# fdcanusb.net
KiCad netlist of a schematic drawn in EAGLE
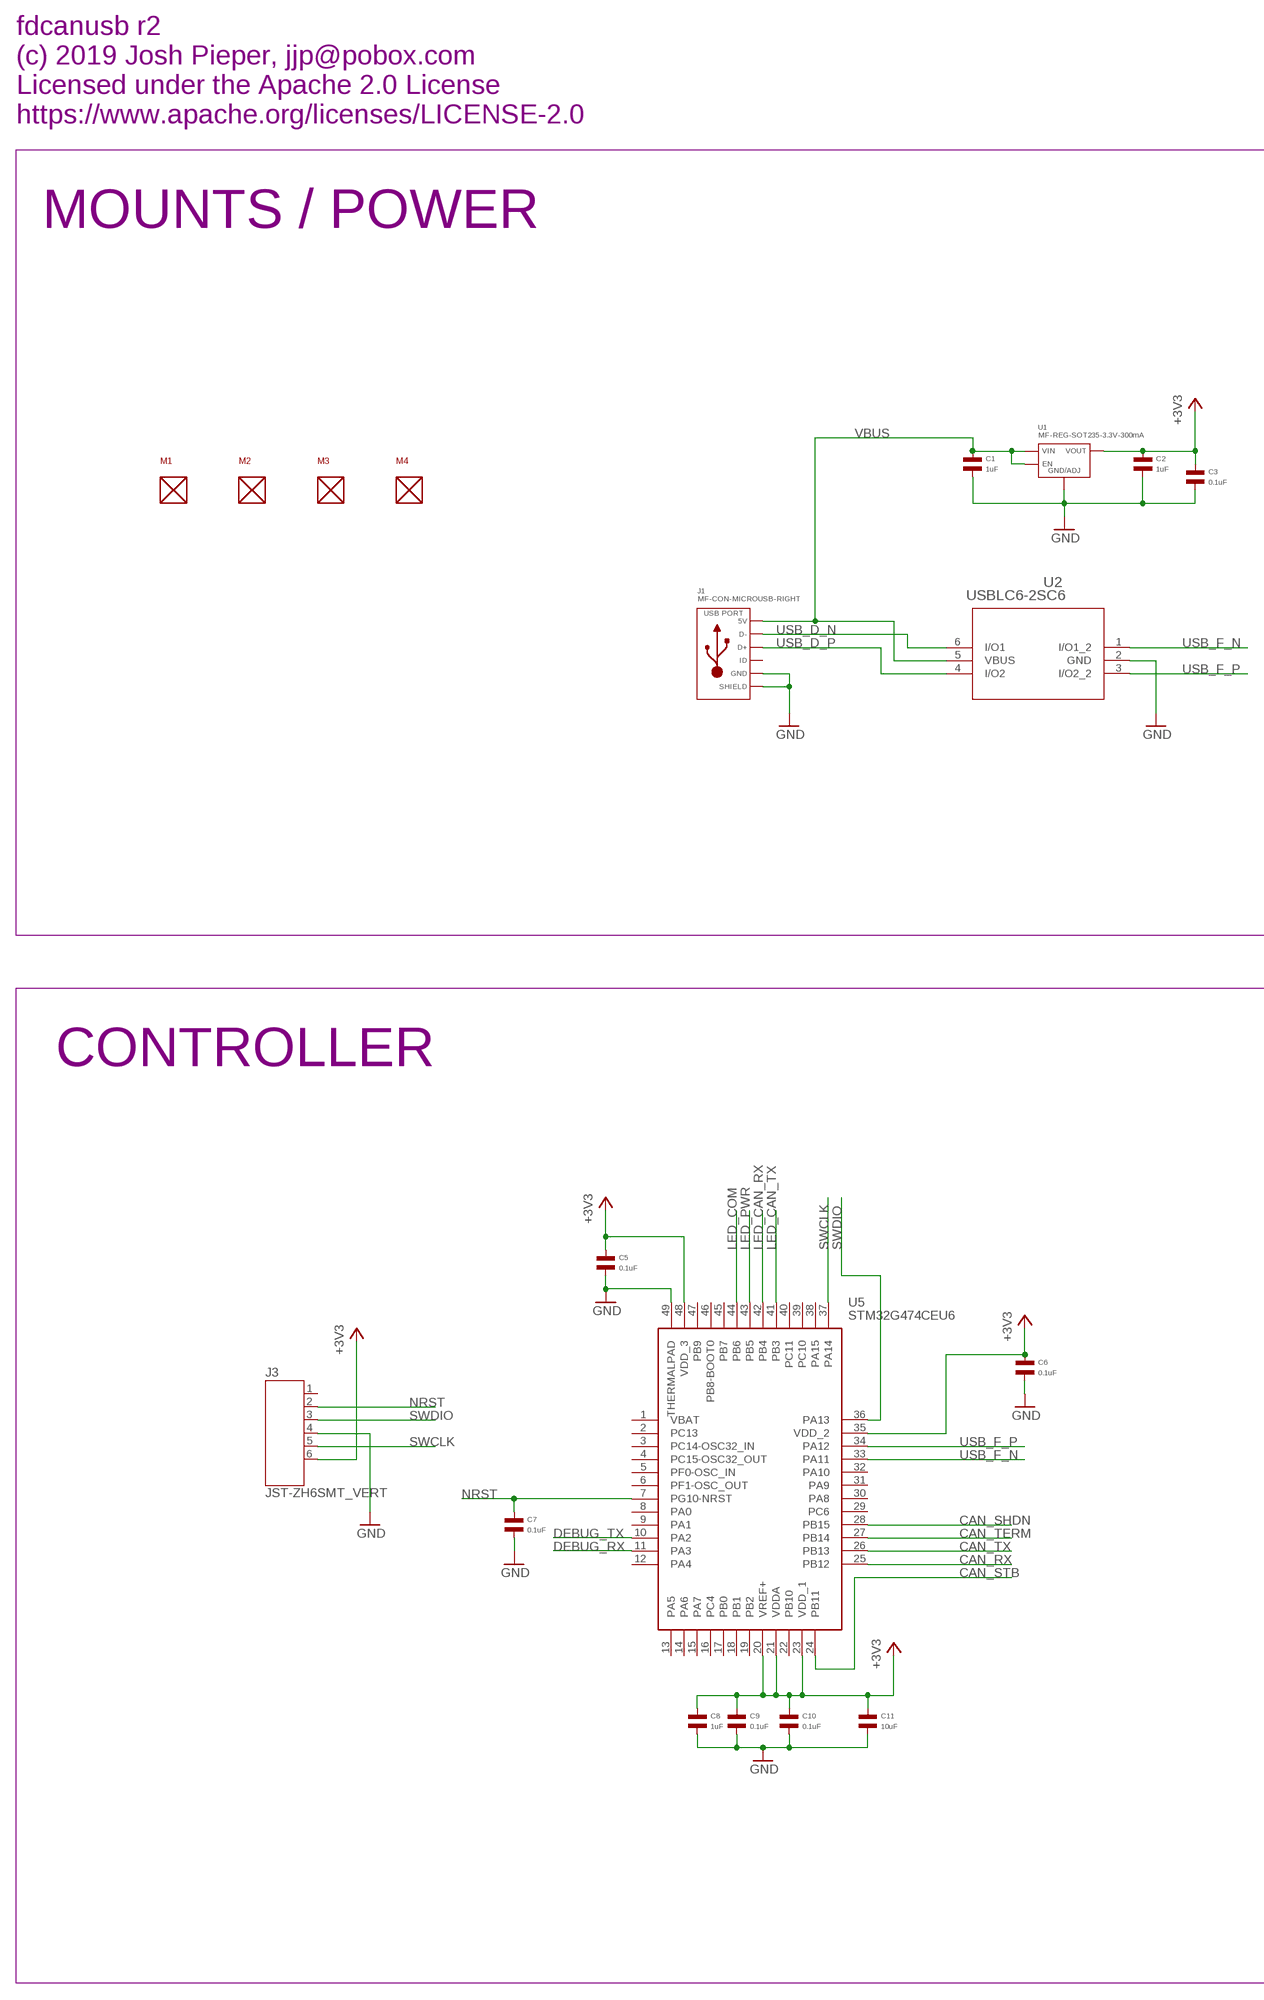
[diagram p0: schematic, sheet 1, part 1 of 2]
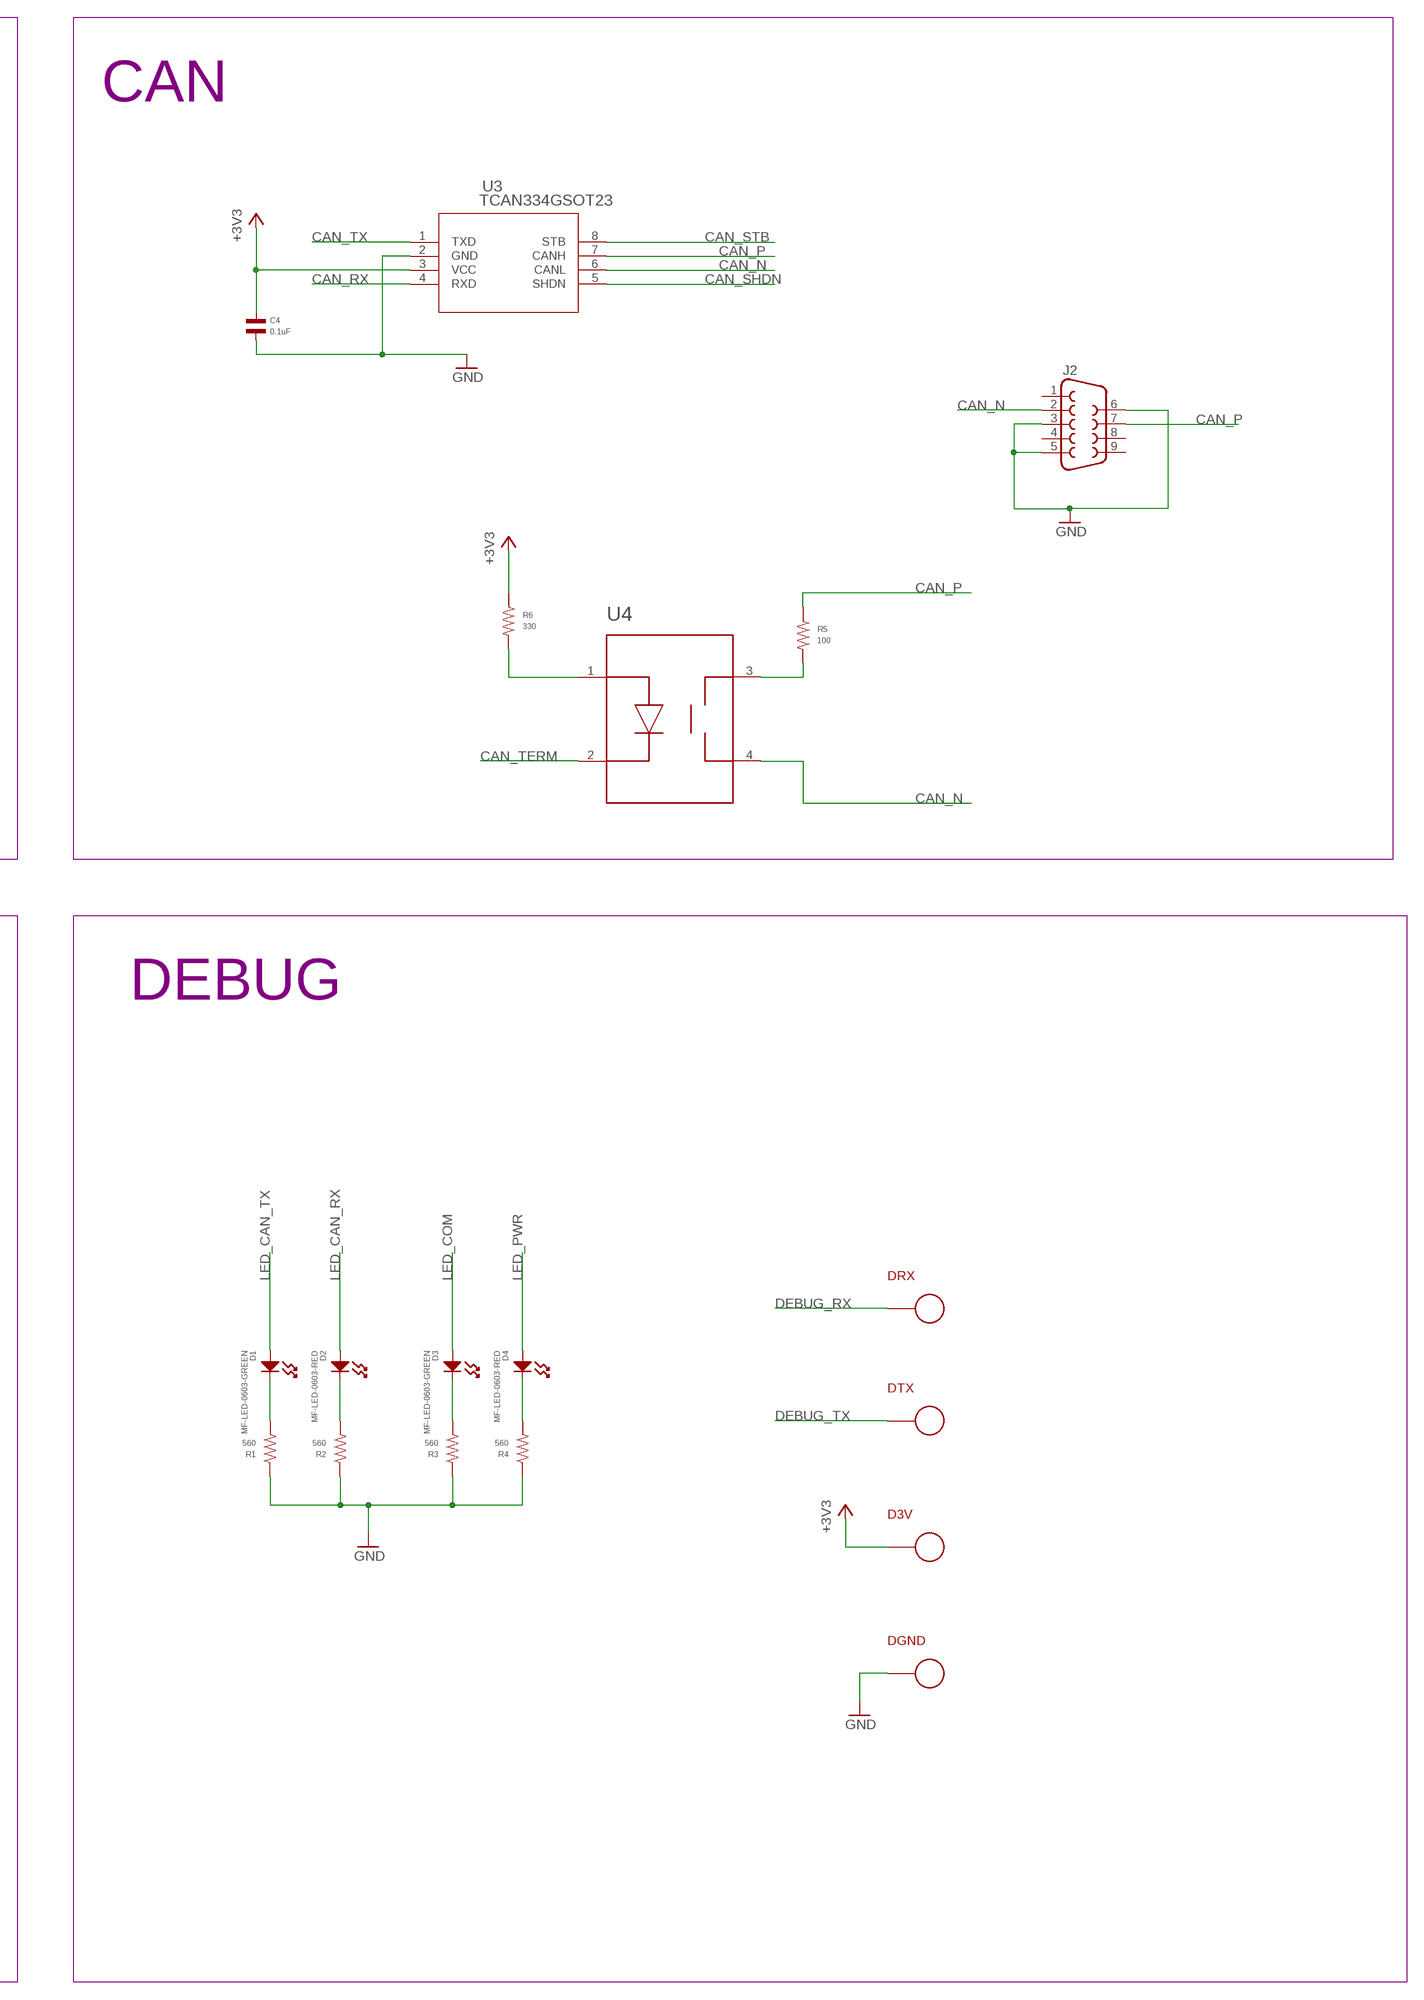
[diagram p1: schematic, sheet 1, part 2 of 2]

(export (version "E")
  (design (tool "Eeschema 10.0.6"))
  (components
    (comp (ref "C1")
      (value "1uF")
      (footprint "eagle-import:C0603")
      (fields (field (name "HOUSEPART") "YES") (field (name "MPN") "MF-CAP-0603-1uF"))
      (libsource (lib "eagle-import") (part "CAPACITOR_NP_0603"))
    )
    (comp (ref "C2")
      (value "1uF")
      (footprint "eagle-import:C0603")
      (fields (field (name "HOUSEPART") "YES") (field (name "MPN") "MF-CAP-0603-1uF"))
      (libsource (lib "eagle-import") (part "CAPACITOR_NP_0603"))
    )
    (comp (ref "C3")
      (value "0.1uF")
      (footprint "eagle-import:C0402")
      (fields (field (name "HOUSEPART") "YES") (field (name "MPN") "MF-CAP-0402-0.1uF"))
      (libsource (lib "eagle-import") (part "CAPACITOR_NP_0402"))
    )
    (comp (ref "C4")
      (value "0.1uF")
      (footprint "eagle-import:C0402")
      (fields (field (name "HOUSEPART") "YES") (field (name "MPN") "MF-CAP-0402-0.1uF"))
      (libsource (lib "eagle-import") (part "CAPACITOR_NP_0402"))
    )
    (comp (ref "C5")
      (value "0.1uF")
      (footprint "eagle-import:C0402")
      (fields (field (name "HOUSEPART") "YES") (field (name "MPN") "MF-CAP-0402-0.1uF"))
      (libsource (lib "eagle-import") (part "CAPACITOR_NP_0402"))
    )
    (comp (ref "C6")
      (value "0.1uF")
      (footprint "eagle-import:C0402")
      (fields (field (name "HOUSEPART") "YES") (field (name "MPN") "MF-CAP-0402-0.1uF"))
      (libsource (lib "eagle-import") (part "CAPACITOR_NP_0402"))
    )
    (comp (ref "C7")
      (value "0.1uF")
      (footprint "eagle-import:C0402")
      (fields (field (name "HOUSEPART") "YES") (field (name "MPN") "MF-CAP-0402-0.1uF"))
      (libsource (lib "eagle-import") (part "CAPACITOR_NP_0402"))
    )
    (comp (ref "C8")
      (value "1uF")
      (footprint "eagle-import:C0603")
      (fields (field (name "HOUSEPART") "YES") (field (name "MPN") "MF-CAP-0603-1uF"))
      (libsource (lib "eagle-import") (part "CAPACITOR_NP_0603"))
    )
    (comp (ref "C9")
      (value "0.1uF")
      (footprint "eagle-import:C0402")
      (fields (field (name "HOUSEPART") "YES") (field (name "MPN") "MF-CAP-0402-0.1uF"))
      (libsource (lib "eagle-import") (part "CAPACITOR_NP_0402"))
    )
    (comp (ref "C10")
      (value "0.1uF")
      (footprint "eagle-import:C0402")
      (fields (field (name "HOUSEPART") "YES") (field (name "MPN") "MF-CAP-0402-0.1uF"))
      (libsource (lib "eagle-import") (part "CAPACITOR_NP_0402"))
    )
    (comp (ref "C11")
      (value "10uF")
      (footprint "eagle-import:C1206")
      (fields (field (name "HOUSEPART") "YES") (field (name "MPN") "MF-CAP-1206-10uF"))
      (libsource (lib "eagle-import") (part "CAPACITOR_NP_1206"))
    )
    (comp (ref "D1")
      (value "MF-LED-0603-GREEN")
      (footprint "eagle-import:LED0603")
      (fields (field (name "HOUSEPART") "YES"))
      (libsource (lib "eagle-import") (part "LED_SINGLE-0603-GREEN"))
    )
    (comp (ref "D2")
      (value "MF-LED-0603-RED")
      (footprint "eagle-import:LED0603")
      (fields (field (name "HOUSEPART") "YES"))
      (libsource (lib "eagle-import") (part "LED_SINGLE-0603-RED"))
    )
    (comp (ref "D3")
      (value "MF-LED-0603-GREEN")
      (footprint "eagle-import:LED0603")
      (fields (field (name "HOUSEPART") "YES"))
      (libsource (lib "eagle-import") (part "LED_SINGLE-0603-GREEN"))
    )
    (comp (ref "D3V")
      (value "PAD24AWG_PAD")
      (footprint "eagle-import:24AWG_PAD")
      (libsource (lib "eagle-import") (part "PAD24AWG_PAD"))
    )
    (comp (ref "D4")
      (value "MF-LED-0603-RED")
      (footprint "eagle-import:LED0603")
      (fields (field (name "HOUSEPART") "YES"))
      (libsource (lib "eagle-import") (part "LED_SINGLE-0603-RED"))
    )
    (comp (ref "DGND")
      (value "PAD24AWG_PAD")
      (footprint "eagle-import:24AWG_PAD")
      (libsource (lib "eagle-import") (part "PAD24AWG_PAD"))
    )
    (comp (ref "DRX")
      (value "PAD24AWG_PAD")
      (footprint "eagle-import:24AWG_PAD")
      (libsource (lib "eagle-import") (part "PAD24AWG_PAD"))
    )
    (comp (ref "DTX")
      (value "PAD24AWG_PAD")
      (footprint "eagle-import:24AWG_PAD")
      (libsource (lib "eagle-import") (part "PAD24AWG_PAD"))
    )
    (comp (ref "J1")
      (value "MF-CON-MICROUSB-RIGHT")
      (footprint "eagle-import:MICROUSB-RIGHT")
      (fields (field (name "HOUSEPART") "YES"))
      (libsource (lib "eagle-import") (part "USB_MICRO_RIGHT"))
    )
    (comp (ref "J2")
      (value "F09H")
      (footprint "eagle-import:F09H")
      (fields (field (name "MF") "Assmann WSW Components") (field (name "MPN") "AE10968-ND"))
      (libsource (lib "eagle-import") (part "F09H"))
    )
    (comp (ref "J3")
      (value "JST-ZH6SMT_VERT")
      (footprint "eagle-import:JST_B6B-ZR-SM4-TF(LF)(SN)")
      (fields (field (name "MF") "JST") (field (name "MPN") "B6B-ZR-SM4-TF(LF)(SN)"))
      (libsource (lib "eagle-import") (part "JST-ZH6SMT_VERT"))
    )
    (comp (ref "M1")
      (value "MOUNT")
      (footprint "eagle-import:M2.5MOUNT")
      (libsource (lib "eagle-import") (part "MOUNT"))
    )
    (comp (ref "M2")
      (value "MOUNT")
      (footprint "eagle-import:M2.5MOUNT")
      (libsource (lib "eagle-import") (part "MOUNT"))
    )
    (comp (ref "M3")
      (value "MOUNT")
      (footprint "eagle-import:M2.5MOUNT")
      (libsource (lib "eagle-import") (part "MOUNT"))
    )
    (comp (ref "M4")
      (value "MOUNT")
      (footprint "eagle-import:M2.5MOUNT")
      (libsource (lib "eagle-import") (part "MOUNT"))
    )
    (comp (ref "R1")
      (value "560")
      (footprint "eagle-import:R0402")
      (fields (field (name "MPN") "MF-RES-0402-560"))
      (libsource (lib "eagle-import") (part "RESISTOR_0402"))
    )
    (comp (ref "R2")
      (value "560")
      (footprint "eagle-import:R0402")
      (fields (field (name "MPN") "MF-RES-0402-560"))
      (libsource (lib "eagle-import") (part "RESISTOR_0402"))
    )
    (comp (ref "R3")
      (value "560")
      (footprint "eagle-import:R0402")
      (fields (field (name "MPN") "MF-RES-0402-560"))
      (libsource (lib "eagle-import") (part "RESISTOR_0402"))
    )
    (comp (ref "R4")
      (value "560")
      (footprint "eagle-import:R0402")
      (fields (field (name "MPN") "MF-RES-0402-560"))
      (libsource (lib "eagle-import") (part "RESISTOR_0402"))
    )
    (comp (ref "R5")
      (value "100")
      (footprint "eagle-import:R0805")
      (fields (field (name "MPN") "MF-RES-0805-100"))
      (libsource (lib "eagle-import") (part "RESISTOR_0805"))
    )
    (comp (ref "R6")
      (value "330")
      (footprint "eagle-import:R0402")
      (fields (field (name "MPN") "MF-RES-0402-330"))
      (libsource (lib "eagle-import") (part "RESISTOR_0402"))
    )
    (comp (ref "U1")
      (value "MF-REG-SOT235-3.3V-300mA")
      (footprint "eagle-import:SOT-23-5")
      (fields (field (name "HOUSEPART") "YES"))
      (libsource (lib "eagle-import") (part "TLV70233PDBVR"))
    )
    (comp (ref "U2")
      (value "USBLC6-2SC6")
      (footprint "eagle-import:SOT23-6L")
      (fields (field (name "MANUFACTURER_PART_NUMBER") "USBLC62SC6") (field (name "MF") "ST"))
      (libsource (lib "eagle-import") (part "USBLC6-2SC6"))
    )
    (comp (ref "U3")
      (value "TCAN334GSOT23")
      (footprint "eagle-import:SOT23-8")
      (fields (field (name "MF") "TI") (field (name "MPN") "TCAN334GDCNT"))
      (libsource (lib "eagle-import") (part "TCAN334GSOT23"))
    )
    (comp (ref "U4")
      (value "TLP3317")
      (footprint "eagle-import:TLP3317")
      (fields
        (field (name "MF") "TOSHIBA")
        (field (name "MPN") "TLP3317(TP15,F")
        (field (name "MPN_1") "TLP3317")
      )
      (libsource (lib "eagle-import") (part "TLP3317"))
    )
    (comp (ref "U5")
      (value "STM32G474CEU6")
      (footprint "eagle-import:QFN50P700X700X60-49N")
      (fields (field (name "MOUSER_PART_NUMBER") "511-STM32G474CEU6") (field (name "MF") "ST"))
      (libsource (lib "eagle-import") (part "STM32G474CEU6"))
    )
  )
  (nets
    (net (code "1") (name "+3V3") (class "Default")
      (node (ref "C10") (pin "P$1") (pinfunction "P$1_P$1") (pintype "passive"))
      (node (ref "C11") (pin "P$1") (pinfunction "P$1_P$1") (pintype "passive"))
      (node (ref "C2") (pin "P$1") (pinfunction "P$1_P$1") (pintype "passive"))
      (node (ref "C3") (pin "P$1") (pinfunction "P$1_P$1") (pintype "passive"))
      (node (ref "C4") (pin "P$1") (pinfunction "P$1_P$1") (pintype "passive"))
      (node (ref "C5") (pin "P$1") (pinfunction "P$1_P$1") (pintype "passive"))
      (node (ref "C6") (pin "P$1") (pinfunction "P$1_P$1") (pintype "passive"))
      (node (ref "C8") (pin "P$1") (pinfunction "P$1_P$1") (pintype "passive"))
      (node (ref "C9") (pin "P$1") (pinfunction "P$1_P$1") (pintype "passive"))
      (node (ref "D3V") (pin "P$1") (pinfunction "P$1_P$1") (pintype "bidirectional"))
      (node (ref "J3") (pin "6") (pinfunction "6_6") (pintype "passive"))
      (node (ref "R6") (pin "P$1") (pinfunction "P$1_P$1") (pintype "passive"))
      (node (ref "U1") (pin "P$5") (pinfunction "VOUT_P$5") (pintype "bidirectional"))
      (node (ref "U3") (pin "3") (pinfunction "VCC_3") (pintype "power_in"))
      (node (ref "U5") (pin "20") (pinfunction "VREF+_20") (pintype "bidirectional"))
      (node (ref "U5") (pin "21") (pinfunction "VDDA_21") (pintype "bidirectional"))
      (node (ref "U5") (pin "23") (pinfunction "VDD_1_23") (pintype "bidirectional"))
      (node (ref "U5") (pin "35") (pinfunction "VDD_2_35") (pintype "bidirectional"))
      (node (ref "U5") (pin "48") (pinfunction "VDD_3_48") (pintype "bidirectional"))
    )
    (net (code "2") (name "/CAN_N") (class "Default")
      (node (ref "J2") (pin "2") (pinfunction "2_2") (pintype "passive"))
      (node (ref "U3") (pin "6") (pinfunction "CANL_6") (pintype "bidirectional"))
      (node (ref "U4") (pin "4") (pinfunction "SW2_4") (pintype "bidirectional"))
    )
    (net (code "3") (name "/CAN_P") (class "Default")
      (node (ref "J2") (pin "7") (pinfunction "7_7") (pintype "passive"))
      (node (ref "R5") (pin "P$1") (pinfunction "P$1_P$1") (pintype "passive"))
      (node (ref "U3") (pin "7") (pinfunction "CANH_7") (pintype "bidirectional"))
    )
    (net (code "4") (name "/CAN_RX") (class "Default")
      (node (ref "U3") (pin "4") (pinfunction "RXD_4") (pintype "output"))
      (node (ref "U5") (pin "25") (pinfunction "PB12_25") (pintype "bidirectional"))
    )
    (net (code "5") (name "/CAN_SHDN") (class "Default")
      (node (ref "U3") (pin "5") (pinfunction "SHDN_5") (pintype "input"))
      (node (ref "U5") (pin "28") (pinfunction "PB15_28") (pintype "bidirectional"))
    )
    (net (code "6") (name "/CAN_STB") (class "Default")
      (node (ref "U3") (pin "8") (pinfunction "STB_8") (pintype "input"))
      (node (ref "U5") (pin "24") (pinfunction "PB11_24") (pintype "bidirectional"))
    )
    (net (code "7") (name "/CAN_TERM") (class "Default")
      (node (ref "U4") (pin "2") (pinfunction "CATHODE_2") (pintype "bidirectional"))
      (node (ref "U5") (pin "27") (pinfunction "PB14_27") (pintype "bidirectional"))
    )
    (net (code "8") (name "/CAN_TX") (class "Default")
      (node (ref "U3") (pin "1") (pinfunction "TXD_1") (pintype "input"))
      (node (ref "U5") (pin "26") (pinfunction "PB13_26") (pintype "bidirectional"))
    )
    (net (code "9") (name "/DEBUG_RX") (class "Default")
      (node (ref "DRX") (pin "P$1") (pinfunction "P$1_P$1") (pintype "bidirectional"))
      (node (ref "U5") (pin "11") (pinfunction "PA3_11") (pintype "bidirectional"))
    )
    (net (code "10") (name "/DEBUG_TX") (class "Default")
      (node (ref "DTX") (pin "P$1") (pinfunction "P$1_P$1") (pintype "bidirectional"))
      (node (ref "U5") (pin "10") (pinfunction "PA2_10") (pintype "bidirectional"))
    )
    (net (code "11") (name "/LED_CAN_RX") (class "Default")
      (node (ref "D2") (pin "ANODE") (pinfunction "ANODE_ANODE") (pintype "power_in"))
      (node (ref "U5") (pin "42") (pinfunction "PB4_42") (pintype "bidirectional"))
    )
    (net (code "12") (name "/LED_CAN_TX") (class "Default")
      (node (ref "D1") (pin "ANODE") (pinfunction "ANODE_ANODE") (pintype "power_in"))
      (node (ref "U5") (pin "41") (pinfunction "PB3_41") (pintype "bidirectional"))
    )
    (net (code "13") (name "/LED_COM") (class "Default")
      (node (ref "D3") (pin "ANODE") (pinfunction "ANODE_ANODE") (pintype "power_in"))
      (node (ref "U5") (pin "44") (pinfunction "PB6_44") (pintype "bidirectional"))
    )
    (net (code "14") (name "/LED_PWR") (class "Default")
      (node (ref "D4") (pin "ANODE") (pinfunction "ANODE_ANODE") (pintype "power_in"))
      (node (ref "U5") (pin "43") (pinfunction "PB5_43") (pintype "bidirectional"))
    )
    (net (code "15") (name "/NRST") (class "Default")
      (node (ref "C7") (pin "P$1") (pinfunction "P$1_P$1") (pintype "passive"))
      (node (ref "J3") (pin "2") (pinfunction "2_2") (pintype "passive"))
      (node (ref "U5") (pin "7") (pinfunction "PG10-NRST_7") (pintype "bidirectional"))
    )
    (net (code "16") (name "/SWCLK") (class "Default")
      (node (ref "J3") (pin "5") (pinfunction "5_5") (pintype "passive"))
      (node (ref "U5") (pin "37") (pinfunction "PA14_37") (pintype "bidirectional"))
    )
    (net (code "17") (name "/SWDIO") (class "Default")
      (node (ref "J3") (pin "3") (pinfunction "3_3") (pintype "passive"))
      (node (ref "U5") (pin "36") (pinfunction "PA13_36") (pintype "bidirectional"))
    )
    (net (code "18") (name "/USB_D_N") (class "Default")
      (node (ref "J1") (pin "2") (pinfunction "D-_2") (pintype "bidirectional"))
      (node (ref "U2") (pin "6") (pinfunction "I/O1_6") (pintype "bidirectional"))
    )
    (net (code "19") (name "/USB_D_P") (class "Default")
      (node (ref "J1") (pin "3") (pinfunction "D+_3") (pintype "bidirectional"))
      (node (ref "U2") (pin "4") (pinfunction "I/O2_4") (pintype "bidirectional"))
    )
    (net (code "20") (name "/USB_F_N") (class "Default")
      (node (ref "U2") (pin "1") (pinfunction "I/O1_2_1") (pintype "bidirectional"))
      (node (ref "U5") (pin "33") (pinfunction "PA11_33") (pintype "bidirectional"))
    )
    (net (code "21") (name "/USB_F_P") (class "Default")
      (node (ref "U2") (pin "3") (pinfunction "I/O2_2_3") (pintype "bidirectional"))
      (node (ref "U5") (pin "34") (pinfunction "PA12_34") (pintype "bidirectional"))
    )
    (net (code "22") (name "/VBUS") (class "Default")
      (node (ref "C1") (pin "P$1") (pinfunction "P$1_P$1") (pintype "passive"))
      (node (ref "J1") (pin "1") (pinfunction "5V_1") (pintype "power_in"))
      (node (ref "U1") (pin "P$1") (pinfunction "VIN_P$1") (pintype "bidirectional"))
      (node (ref "U1") (pin "P$3") (pinfunction "EN_P$3") (pintype "bidirectional"))
      (node (ref "U2") (pin "5") (pinfunction "VBUS_5") (pintype "power_in"))
    )
    (net (code "23") (name "GND") (class "Default")
      (node (ref "C1") (pin "P$2") (pinfunction "P$2_P$2") (pintype "passive"))
      (node (ref "C10") (pin "P$2") (pinfunction "P$2_P$2") (pintype "passive"))
      (node (ref "C11") (pin "P$2") (pinfunction "P$2_P$2") (pintype "passive"))
      (node (ref "C2") (pin "P$2") (pinfunction "P$2_P$2") (pintype "passive"))
      (node (ref "C3") (pin "P$2") (pinfunction "P$2_P$2") (pintype "passive"))
      (node (ref "C4") (pin "P$2") (pinfunction "P$2_P$2") (pintype "passive"))
      (node (ref "C5") (pin "P$2") (pinfunction "P$2_P$2") (pintype "passive"))
      (node (ref "C6") (pin "P$2") (pinfunction "P$2_P$2") (pintype "passive"))
      (node (ref "C7") (pin "P$2") (pinfunction "P$2_P$2") (pintype "passive"))
      (node (ref "C8") (pin "P$2") (pinfunction "P$2_P$2") (pintype "passive"))
      (node (ref "C9") (pin "P$2") (pinfunction "P$2_P$2") (pintype "passive"))
      (node (ref "DGND") (pin "P$1") (pinfunction "P$1_P$1") (pintype "bidirectional"))
      (node (ref "J1") (pin "5") (pinfunction "GND_5") (pintype "power_in"))
      (node (ref "J1") (pin "S1") (pinfunction "SLD_S1") (pintype "power_in"))
      (node (ref "J1") (pin "S2") (pinfunction "SLD_S2") (pintype "power_in"))
      (node (ref "J1") (pin "S3") (pinfunction "SLD_S3") (pintype "power_in"))
      (node (ref "J1") (pin "S4") (pinfunction "SLD_S4") (pintype "power_in"))
      (node (ref "J1") (pin "S5") (pinfunction "SLD_S5") (pintype "power_in"))
      (node (ref "J1") (pin "S6") (pinfunction "SLD_S6") (pintype "power_in"))
      (node (ref "J2") (pin "3") (pinfunction "3_3") (pintype "passive"))
      (node (ref "J2") (pin "5") (pinfunction "5_5") (pintype "passive"))
      (node (ref "J2") (pin "6") (pinfunction "6_6") (pintype "passive"))
      (node (ref "J3") (pin "4") (pinfunction "4_4") (pintype "passive"))
      (node (ref "R1") (pin "P$1") (pinfunction "P$1_P$1") (pintype "passive"))
      (node (ref "R2") (pin "P$1") (pinfunction "P$1_P$1") (pintype "passive"))
      (node (ref "R3") (pin "P$1") (pinfunction "P$1_P$1") (pintype "passive"))
      (node (ref "R4") (pin "P$1") (pinfunction "P$1_P$1") (pintype "passive"))
      (node (ref "U1") (pin "P$2") (pinfunction "GND/ADJ_P$2") (pintype "bidirectional"))
      (node (ref "U2") (pin "2") (pinfunction "GND_2") (pintype "power_in"))
      (node (ref "U3") (pin "2") (pinfunction "GND_2") (pintype "power_in"))
      (node (ref "U5") (pin "49") (pinfunction "THERMALPAD_49") (pintype "bidirectional"))
    )
    (net (code "24") (name "Net-(D1-PadCATHODE)") (class "Default")
      (node (ref "D1") (pin "CATHODE") (pinfunction "CATHODE_CATHODE") (pintype "power_in"))
      (node (ref "R1") (pin "P$2") (pinfunction "P$2_P$2") (pintype "passive"))
    )
    (net (code "25") (name "Net-(D2-PadCATHODE)") (class "Default")
      (node (ref "D2") (pin "CATHODE") (pinfunction "CATHODE_CATHODE") (pintype "power_in"))
      (node (ref "R2") (pin "P$2") (pinfunction "P$2_P$2") (pintype "passive"))
    )
    (net (code "26") (name "Net-(D3-PadCATHODE)") (class "Default")
      (node (ref "D3") (pin "CATHODE") (pinfunction "CATHODE_CATHODE") (pintype "power_in"))
      (node (ref "R3") (pin "P$2") (pinfunction "P$2_P$2") (pintype "passive"))
    )
    (net (code "27") (name "Net-(D4-PadCATHODE)") (class "Default")
      (node (ref "D4") (pin "CATHODE") (pinfunction "CATHODE_CATHODE") (pintype "power_in"))
      (node (ref "R4") (pin "P$2") (pinfunction "P$2_P$2") (pintype "passive"))
    )
    (net (code "28") (name "Net-(U4-ANODE)") (class "Default")
      (node (ref "R6") (pin "P$2") (pinfunction "P$2_P$2") (pintype "passive"))
      (node (ref "U4") (pin "1") (pinfunction "ANODE_1") (pintype "bidirectional"))
    )
    (net (code "29") (name "Net-(U4-SW1)") (class "Default")
      (node (ref "R5") (pin "P$2") (pinfunction "P$2_P$2") (pintype "passive"))
      (node (ref "U4") (pin "3") (pinfunction "SW1_3") (pintype "bidirectional"))
    )
    (net (code "30") (name "unconnected-(J1-ID-Pad4)") (class "Default")
      (node (ref "J1") (pin "4") (pinfunction "ID_4") (pintype "bidirectional"))
    )
    (net (code "31") (name "unconnected-(J2-Pad1)") (class "Default")
      (node (ref "J2") (pin "1") (pinfunction "1_1") (pintype "passive"))
    )
    (net (code "32") (name "unconnected-(J2-Pad4)") (class "Default")
      (node (ref "J2") (pin "4") (pinfunction "4_4") (pintype "passive"))
    )
    (net (code "33") (name "unconnected-(J2-Pad8)") (class "Default")
      (node (ref "J2") (pin "8") (pinfunction "8_8") (pintype "passive"))
    )
    (net (code "34") (name "unconnected-(J2-Pad9)") (class "Default")
      (node (ref "J2") (pin "9") (pinfunction "9_9") (pintype "passive"))
    )
    (net (code "35") (name "unconnected-(J3-Pad1)") (class "Default")
      (node (ref "J3") (pin "1") (pinfunction "1_1") (pintype "passive"))
    )
    (net (code "36") (name "unconnected-(U5-PA0-Pad8)") (class "Default")
      (node (ref "U5") (pin "8") (pinfunction "PA0_8") (pintype "bidirectional"))
    )
    (net (code "37") (name "unconnected-(U5-PA1-Pad9)") (class "Default")
      (node (ref "U5") (pin "9") (pinfunction "PA1_9") (pintype "bidirectional"))
    )
    (net (code "38") (name "unconnected-(U5-PA4-Pad12)") (class "Default")
      (node (ref "U5") (pin "12") (pinfunction "PA4_12") (pintype "bidirectional"))
    )
    (net (code "39") (name "unconnected-(U5-PA5-Pad13)") (class "Default")
      (node (ref "U5") (pin "13") (pinfunction "PA5_13") (pintype "bidirectional"))
    )
    (net (code "40") (name "unconnected-(U5-PA6-Pad14)") (class "Default")
      (node (ref "U5") (pin "14") (pinfunction "PA6_14") (pintype "bidirectional"))
    )
    (net (code "41") (name "unconnected-(U5-PA7-Pad15)") (class "Default")
      (node (ref "U5") (pin "15") (pinfunction "PA7_15") (pintype "bidirectional"))
    )
    (net (code "42") (name "unconnected-(U5-PA8-Pad30)") (class "Default")
      (node (ref "U5") (pin "30") (pinfunction "PA8_30") (pintype "bidirectional"))
    )
    (net (code "43") (name "unconnected-(U5-PA9-Pad31)") (class "Default")
      (node (ref "U5") (pin "31") (pinfunction "PA9_31") (pintype "bidirectional"))
    )
    (net (code "44") (name "unconnected-(U5-PA10-Pad32)") (class "Default")
      (node (ref "U5") (pin "32") (pinfunction "PA10_32") (pintype "bidirectional"))
    )
    (net (code "45") (name "unconnected-(U5-PA15-Pad38)") (class "Default")
      (node (ref "U5") (pin "38") (pinfunction "PA15_38") (pintype "bidirectional"))
    )
    (net (code "46") (name "unconnected-(U5-PB0-Pad17)") (class "Default")
      (node (ref "U5") (pin "17") (pinfunction "PB0_17") (pintype "bidirectional"))
    )
    (net (code "47") (name "unconnected-(U5-PB1-Pad18)") (class "Default")
      (node (ref "U5") (pin "18") (pinfunction "PB1_18") (pintype "bidirectional"))
    )
    (net (code "48") (name "unconnected-(U5-PB2-Pad19)") (class "Default")
      (node (ref "U5") (pin "19") (pinfunction "PB2_19") (pintype "bidirectional"))
    )
    (net (code "49") (name "unconnected-(U5-PB7-Pad45)") (class "Default")
      (node (ref "U5") (pin "45") (pinfunction "PB7_45") (pintype "bidirectional"))
    )
    (net (code "50") (name "unconnected-(U5-PB8-BOOT0-Pad46)") (class "Default")
      (node (ref "U5") (pin "46") (pinfunction "PB8-BOOT0_46") (pintype "bidirectional"))
    )
    (net (code "51") (name "unconnected-(U5-PB9-Pad47)") (class "Default")
      (node (ref "U5") (pin "47") (pinfunction "PB9_47") (pintype "bidirectional"))
    )
    (net (code "52") (name "unconnected-(U5-PB10-Pad22)") (class "Default")
      (node (ref "U5") (pin "22") (pinfunction "PB10_22") (pintype "bidirectional"))
    )
    (net (code "53") (name "unconnected-(U5-PC4-Pad16)") (class "Default")
      (node (ref "U5") (pin "16") (pinfunction "PC4_16") (pintype "bidirectional"))
    )
    (net (code "54") (name "unconnected-(U5-PC6-Pad29)") (class "Default")
      (node (ref "U5") (pin "29") (pinfunction "PC6_29") (pintype "bidirectional"))
    )
    (net (code "55") (name "unconnected-(U5-PC10-Pad39)") (class "Default")
      (node (ref "U5") (pin "39") (pinfunction "PC10_39") (pintype "bidirectional"))
    )
    (net (code "56") (name "unconnected-(U5-PC11-Pad40)") (class "Default")
      (node (ref "U5") (pin "40") (pinfunction "PC11_40") (pintype "bidirectional"))
    )
    (net (code "57") (name "unconnected-(U5-PC13-Pad2)") (class "Default")
      (node (ref "U5") (pin "2") (pinfunction "PC13_2") (pintype "bidirectional"))
    )
    (net (code "58") (name "unconnected-(U5-PC14-OSC32_IN-Pad3)") (class "Default")
      (node (ref "U5") (pin "3") (pinfunction "PC14-OSC32_IN_3") (pintype "bidirectional"))
    )
    (net (code "59") (name "unconnected-(U5-PC15-OSC32_OUT-Pad4)") (class "Default")
      (node (ref "U5") (pin "4") (pinfunction "PC15-OSC32_OUT_4") (pintype "bidirectional"))
    )
    (net (code "60") (name "unconnected-(U5-PF0-OSC_IN-Pad5)") (class "Default")
      (node (ref "U5") (pin "5") (pinfunction "PF0-OSC_IN_5") (pintype "bidirectional"))
    )
    (net (code "61") (name "unconnected-(U5-PF1-OSC_OUT-Pad6)") (class "Default")
      (node (ref "U5") (pin "6") (pinfunction "PF1-OSC_OUT_6") (pintype "bidirectional"))
    )
    (net (code "62") (name "unconnected-(U5-VBAT-Pad1)") (class "Default")
      (node (ref "U5") (pin "1") (pinfunction "VBAT_1") (pintype "bidirectional"))
    )
  )
)
